# YOTSUBA__X_EM_ver_3_0.net
KiCad netlist of a schematic drawn in EAGLE
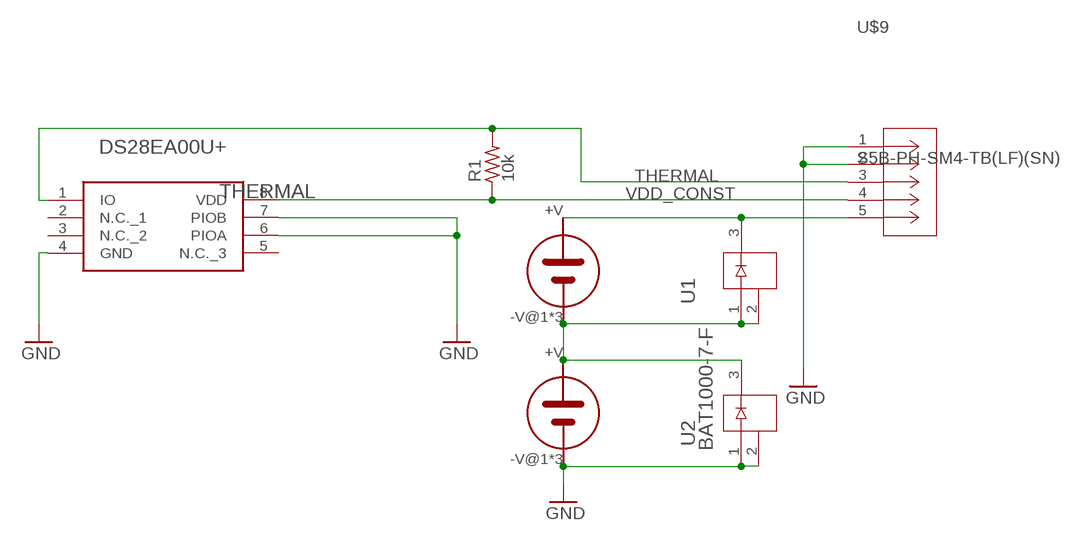
[diagram p0: schematic, sheet 1]

(export (version "E")
  (design (tool "Eeschema 10.0.6"))
  (components
    (comp (ref "R1")
      (value "10k")
      (footprint "eagle-import:R0805")
      (libsource (lib "eagle-import") (part "R-US_R0805"))
    )
    (comp (ref "THERMAL")
      (value "DS28EA00U+")
      (footprint "eagle-import:SOP65P490X110-8N")
      (fields (field (name "MOUSER_PART_NUMBER") "700-DS28EA00U"))
      (libsource (lib "eagle-import") (part "DS28EA00U+"))
    )
    (comp (ref "U$2")
      (value "3G30A")
      (footprint "eagle-import:SOLAR_3G30A")
      (libsource (lib "eagle-import") (part "3G30A"))
    )
    (comp (ref "U$3")
      (value "3G30A")
      (footprint "eagle-import:SOLAR_3G30A")
      (libsource (lib "eagle-import") (part "3G30A"))
    )
    (comp (ref "U$9")
      (value "S5B-PH-SM4-TB(LF)(SN)")
      (footprint "eagle-import:CONN_S5B-PH-SM4-TB_JST")
      (fields (field (name "COPYRIGHT") "Copyright (C) 2023 Ultra Librarian. All rights reserved."))
      (libsource (lib "eagle-import") (part "S5B-PH-SM4-TB(LF)(SN)"))
    )
    (comp (ref "U1")
      (value "BAT1000-7-F")
      (footprint "eagle-import:SOT23_BAT_DIO")
      (fields (field (name "COPYRIGHT") "Copyright (C) 2023 Ultra Librarian. All rights reserved."))
      (libsource (lib "eagle-import") (part "BAT1000-7-F"))
    )
    (comp (ref "U2")
      (value "BAT1000-7-F")
      (footprint "eagle-import:SOT23_BAT_DIO")
      (fields (field (name "COPYRIGHT") "Copyright (C) 2023 Ultra Librarian. All rights reserved."))
      (libsource (lib "eagle-import") (part "BAT1000-7-F"))
    )
  )
  (nets
    (net (code "1") (name "/THERMAL") (class "Default")
      (node (ref "R1") (pin "2") (pinfunction "2_2") (pintype "passive"))
      (node (ref "THERMAL") (pin "1") (pinfunction "IO_1") (pintype "bidirectional"))
      (node (ref "U$9") (pin "3") (pinfunction "3_3") (pintype "passive"))
    )
    (net (code "2") (name "/VDD_CONST") (class "Default")
      (node (ref "R1") (pin "1") (pinfunction "1_1") (pintype "passive"))
      (node (ref "THERMAL") (pin "8") (pinfunction "VDD_8") (pintype "bidirectional"))
      (node (ref "U$9") (pin "4") (pinfunction "4_4") (pintype "passive"))
    )
    (net (code "3") (name "GND") (class "Default")
      (node (ref "THERMAL") (pin "4") (pinfunction "GND_4") (pintype "bidirectional"))
      (node (ref "THERMAL") (pin "6") (pinfunction "PIOA_6") (pintype "bidirectional"))
      (node (ref "THERMAL") (pin "7") (pinfunction "PIOB_7") (pintype "bidirectional"))
      (node (ref "U$3") (pin "-V@1") (pinfunction "-V_-V@1") (pintype "bidirectional"))
      (node (ref "U$3") (pin "-V@2") (pinfunction "-V_-V@2") (pintype "bidirectional"))
      (node (ref "U$3") (pin "-V@3") (pinfunction "-V_-V@3") (pintype "bidirectional"))
      (node (ref "U$9") (pin "1") (pinfunction "1_1") (pintype "passive"))
      (node (ref "U$9") (pin "2") (pinfunction "2_2") (pintype "passive"))
      (node (ref "U2") (pin "1") (pinfunction "1_1") (pintype "passive"))
      (node (ref "U2") (pin "2") (pinfunction "2_2") (pintype "passive"))
    )
    (net (code "4") (name "Net-(U$2--V-Pad-V@1)") (class "Default")
      (node (ref "U$2") (pin "-V@1") (pinfunction "-V_-V@1") (pintype "bidirectional"))
      (node (ref "U$2") (pin "-V@2") (pinfunction "-V_-V@2") (pintype "bidirectional"))
      (node (ref "U$2") (pin "-V@3") (pinfunction "-V_-V@3") (pintype "bidirectional"))
      (node (ref "U$3") (pin "+V") (pinfunction "+V_+V") (pintype "bidirectional"))
      (node (ref "U1") (pin "1") (pinfunction "1_1") (pintype "passive"))
      (node (ref "U1") (pin "2") (pinfunction "2_2") (pintype "passive"))
      (node (ref "U2") (pin "3") (pinfunction "3_3") (pintype "passive"))
    )
    (net (code "5") (name "Net-(U$2-Pad+V)") (class "Default")
      (node (ref "U$2") (pin "+V") (pinfunction "+V_+V") (pintype "bidirectional"))
      (node (ref "U$9") (pin "5") (pinfunction "5_5") (pintype "passive"))
      (node (ref "U1") (pin "3") (pinfunction "3_3") (pintype "passive"))
    )
    (net (code "6") (name "unconnected-(THERMAL-N.C._1-Pad2)") (class "Default")
      (node (ref "THERMAL") (pin "2") (pinfunction "N.C._1_2") (pintype "bidirectional"))
    )
    (net (code "7") (name "unconnected-(THERMAL-N.C._2-Pad3)") (class "Default")
      (node (ref "THERMAL") (pin "3") (pinfunction "N.C._2_3") (pintype "bidirectional"))
    )
    (net (code "8") (name "unconnected-(THERMAL-N.C._3-Pad5)") (class "Default")
      (node (ref "THERMAL") (pin "5") (pinfunction "N.C._3_5") (pintype "bidirectional"))
    )
  )
)
